# USB_Multiplicator_2025.net
KiCad netlist of a schematic drawn in EAGLE
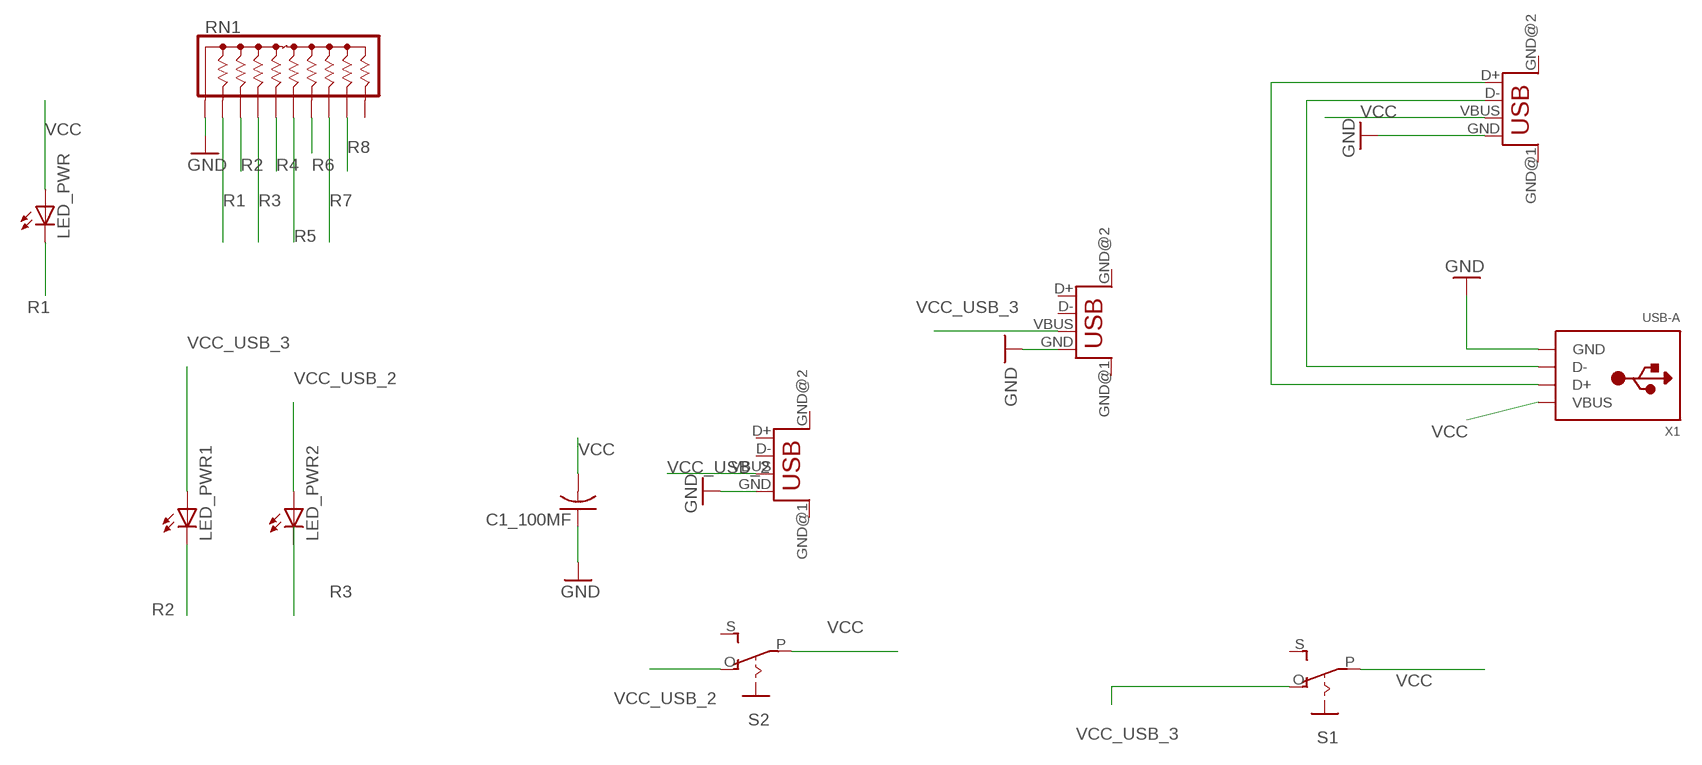
[diagram p0: schematic, sheet 1]

(export (version "E")
  (design (tool "Eeschema 10.0.6"))
  (components
    (comp (ref "C1_100MF")
      (value "C-US025-030X050")
      (footprint "eagle-import:C025-030X050")
      (libsource (lib "eagle-import") (part "C-US025-030X050"))
    )
    (comp (ref "LED_PWR")
      (value "LEDSMT1206")
      (footprint "eagle-import:1206")
      (libsource (lib "eagle-import") (part "LEDSMT1206"))
    )
    (comp (ref "LED_PWR1")
      (value "LEDSMT1206")
      (footprint "eagle-import:1206")
      (libsource (lib "eagle-import") (part "LEDSMT1206"))
    )
    (comp (ref "LED_PWR2")
      (value "LEDSMT1206")
      (footprint "eagle-import:1206")
      (libsource (lib "eagle-import") (part "LEDSMT1206"))
    )
    (comp (ref "RN1")
      (value "4610X")
      (footprint "eagle-import:SIP10")
      (libsource (lib "eagle-import") (part "4610X"))
    )
    (comp (ref "S1")
      (value "EG1218S")
      (footprint "eagle-import:EG1218")
      (libsource (lib "eagle-import") (part "EG1218S"))
    )
    (comp (ref "S2")
      (value "EG1218S")
      (footprint "eagle-import:EG1218")
      (libsource (lib "eagle-import") (part "EG1218S"))
    )
    (comp (ref "USB_OUT_1")
      (value "USB")
      (footprint "eagle-import:USB-FEMALE-A-PTH")
      (libsource (lib "eagle-import") (part "USB"))
    )
    (comp (ref "USB_OUT_2")
      (value "USB")
      (footprint "eagle-import:USB-FEMALE-A-PTH")
      (libsource (lib "eagle-import") (part "USB"))
    )
    (comp (ref "USB_OUT_WITH_DATA_1")
      (value "USB")
      (footprint "eagle-import:USB-FEMALE-A-PTH")
      (libsource (lib "eagle-import") (part "USB"))
    )
    (comp (ref "X1")
      (value "USB-A")
      (footprint "eagle-import:MOLEX_480371000")
      (libsource (lib "eagle-import") (part "USB-A"))
    )
  )
  (nets
    (net (code "1") (name "/R1") (class "Default")
      (node (ref "LED_PWR") (pin "C") (pinfunction "C_C") (pintype "passive"))
      (node (ref "RN1") (pin "2") (pinfunction "2_2") (pintype "passive"))
    )
    (net (code "2") (name "/R2") (class "Default")
      (node (ref "LED_PWR1") (pin "C") (pinfunction "C_C") (pintype "passive"))
      (node (ref "RN1") (pin "3") (pinfunction "3_3") (pintype "passive"))
    )
    (net (code "3") (name "/R3") (class "Default")
      (node (ref "LED_PWR2") (pin "C") (pinfunction "C_C") (pintype "passive"))
      (node (ref "RN1") (pin "4") (pinfunction "4_4") (pintype "passive"))
    )
    (net (code "4") (name "/R4") (class "Default")
      (node (ref "RN1") (pin "5") (pinfunction "5_5") (pintype "passive"))
    )
    (net (code "5") (name "/R5") (class "Default")
      (node (ref "RN1") (pin "6") (pinfunction "6_6") (pintype "passive"))
    )
    (net (code "6") (name "/R6") (class "Default")
      (node (ref "RN1") (pin "7") (pinfunction "7_7") (pintype "passive"))
    )
    (net (code "7") (name "/R7") (class "Default")
      (node (ref "RN1") (pin "8") (pinfunction "8_8") (pintype "passive"))
    )
    (net (code "8") (name "/R8") (class "Default")
      (node (ref "RN1") (pin "9") (pinfunction "9_9") (pintype "passive"))
    )
    (net (code "9") (name "/VCC") (class "Default")
      (node (ref "C1_100MF") (pin "2") (pinfunction "2_2") (pintype "passive"))
      (node (ref "LED_PWR") (pin "A") (pinfunction "A_A") (pintype "passive"))
      (node (ref "S1") (pin "P") (pinfunction "P_P") (pintype "passive"))
      (node (ref "S2") (pin "P") (pinfunction "P_P") (pintype "passive"))
      (node (ref "USB_OUT_WITH_DATA_1") (pin "VBUS") (pinfunction "VBUS_VBUS") (pintype "bidirectional"))
      (node (ref "X1") (pin "1") (pinfunction "VBUS_1") (pintype "power_in"))
    )
    (net (code "10") (name "/VCC_USB_2") (class "Default")
      (node (ref "LED_PWR2") (pin "A") (pinfunction "A_A") (pintype "passive"))
      (node (ref "S2") (pin "O") (pinfunction "O_O") (pintype "passive"))
      (node (ref "USB_OUT_2") (pin "VBUS") (pinfunction "VBUS_VBUS") (pintype "bidirectional"))
    )
    (net (code "11") (name "/VCC_USB_3") (class "Default")
      (node (ref "LED_PWR1") (pin "A") (pinfunction "A_A") (pintype "passive"))
      (node (ref "S1") (pin "O") (pinfunction "O_O") (pintype "passive"))
      (node (ref "USB_OUT_1") (pin "VBUS") (pinfunction "VBUS_VBUS") (pintype "bidirectional"))
    )
    (net (code "12") (name "GND") (class "Default")
      (node (ref "C1_100MF") (pin "1") (pinfunction "1_1") (pintype "passive"))
      (node (ref "RN1") (pin "1") (pinfunction "1_1") (pintype "passive"))
      (node (ref "USB_OUT_1") (pin "GND") (pinfunction "GND_GND") (pintype "bidirectional"))
      (node (ref "USB_OUT_2") (pin "GND") (pinfunction "GND_GND") (pintype "bidirectional"))
      (node (ref "USB_OUT_WITH_DATA_1") (pin "GND") (pinfunction "GND_GND") (pintype "bidirectional"))
      (node (ref "X1") (pin "4") (pinfunction "GND_4") (pintype "power_in"))
    )
    (net (code "13") (name "Net-(X1-D+)") (class "Default")
      (node (ref "USB_OUT_WITH_DATA_1") (pin "D+") (pinfunction "D+_D+") (pintype "bidirectional"))
      (node (ref "X1") (pin "3") (pinfunction "D+_3") (pintype "bidirectional"))
    )
    (net (code "14") (name "Net-(X1-D-)") (class "Default")
      (node (ref "USB_OUT_WITH_DATA_1") (pin "D-") (pinfunction "D-_D-") (pintype "bidirectional"))
      (node (ref "X1") (pin "2") (pinfunction "D-_2") (pintype "bidirectional"))
    )
    (net (code "15") (name "unconnected-(RN1-Pad10)") (class "Default")
      (node (ref "RN1") (pin "10") (pinfunction "10_10") (pintype "passive"))
    )
    (net (code "16") (name "unconnected-(S1-PadS)") (class "Default")
      (node (ref "S1") (pin "S") (pinfunction "S_S") (pintype "passive"))
    )
    (net (code "17") (name "unconnected-(S2-PadS)") (class "Default")
      (node (ref "S2") (pin "S") (pinfunction "S_S") (pintype "passive"))
    )
    (net (code "18") (name "unconnected-(USB_OUT_1-GND-PadGND@1)") (class "Default")
      (node (ref "USB_OUT_1") (pin "GND@1") (pinfunction "GND_GND@1") (pintype "bidirectional"))
    )
    (net (code "19") (name "unconnected-(USB_OUT_1-GND-PadGND@2)") (class "Default")
      (node (ref "USB_OUT_1") (pin "GND@2") (pinfunction "GND_GND@2") (pintype "bidirectional"))
    )
    (net (code "20") (name "unconnected-(USB_OUT_1-PadD+)") (class "Default")
      (node (ref "USB_OUT_1") (pin "D+") (pinfunction "D+_D+") (pintype "bidirectional"))
    )
    (net (code "21") (name "unconnected-(USB_OUT_1-PadD-)") (class "Default")
      (node (ref "USB_OUT_1") (pin "D-") (pinfunction "D-_D-") (pintype "bidirectional"))
    )
    (net (code "22") (name "unconnected-(USB_OUT_2-GND-PadGND@1)") (class "Default")
      (node (ref "USB_OUT_2") (pin "GND@1") (pinfunction "GND_GND@1") (pintype "bidirectional"))
    )
    (net (code "23") (name "unconnected-(USB_OUT_2-GND-PadGND@2)") (class "Default")
      (node (ref "USB_OUT_2") (pin "GND@2") (pinfunction "GND_GND@2") (pintype "bidirectional"))
    )
    (net (code "24") (name "unconnected-(USB_OUT_2-PadD+)") (class "Default")
      (node (ref "USB_OUT_2") (pin "D+") (pinfunction "D+_D+") (pintype "bidirectional"))
    )
    (net (code "25") (name "unconnected-(USB_OUT_2-PadD-)") (class "Default")
      (node (ref "USB_OUT_2") (pin "D-") (pinfunction "D-_D-") (pintype "bidirectional"))
    )
    (net (code "26") (name "unconnected-(USB_OUT_WITH_DATA_1-GND-PadGND@1)") (class "Default")
      (node (ref "USB_OUT_WITH_DATA_1") (pin "GND@1") (pinfunction "GND_GND@1") (pintype "bidirectional"))
    )
    (net (code "27") (name "unconnected-(USB_OUT_WITH_DATA_1-GND-PadGND@2)") (class "Default")
      (node (ref "USB_OUT_WITH_DATA_1") (pin "GND@2") (pinfunction "GND_GND@2") (pintype "bidirectional"))
    )
  )
)
